# Relay_IO.net
KiCad netlist of a schematic drawn in Altium Designer
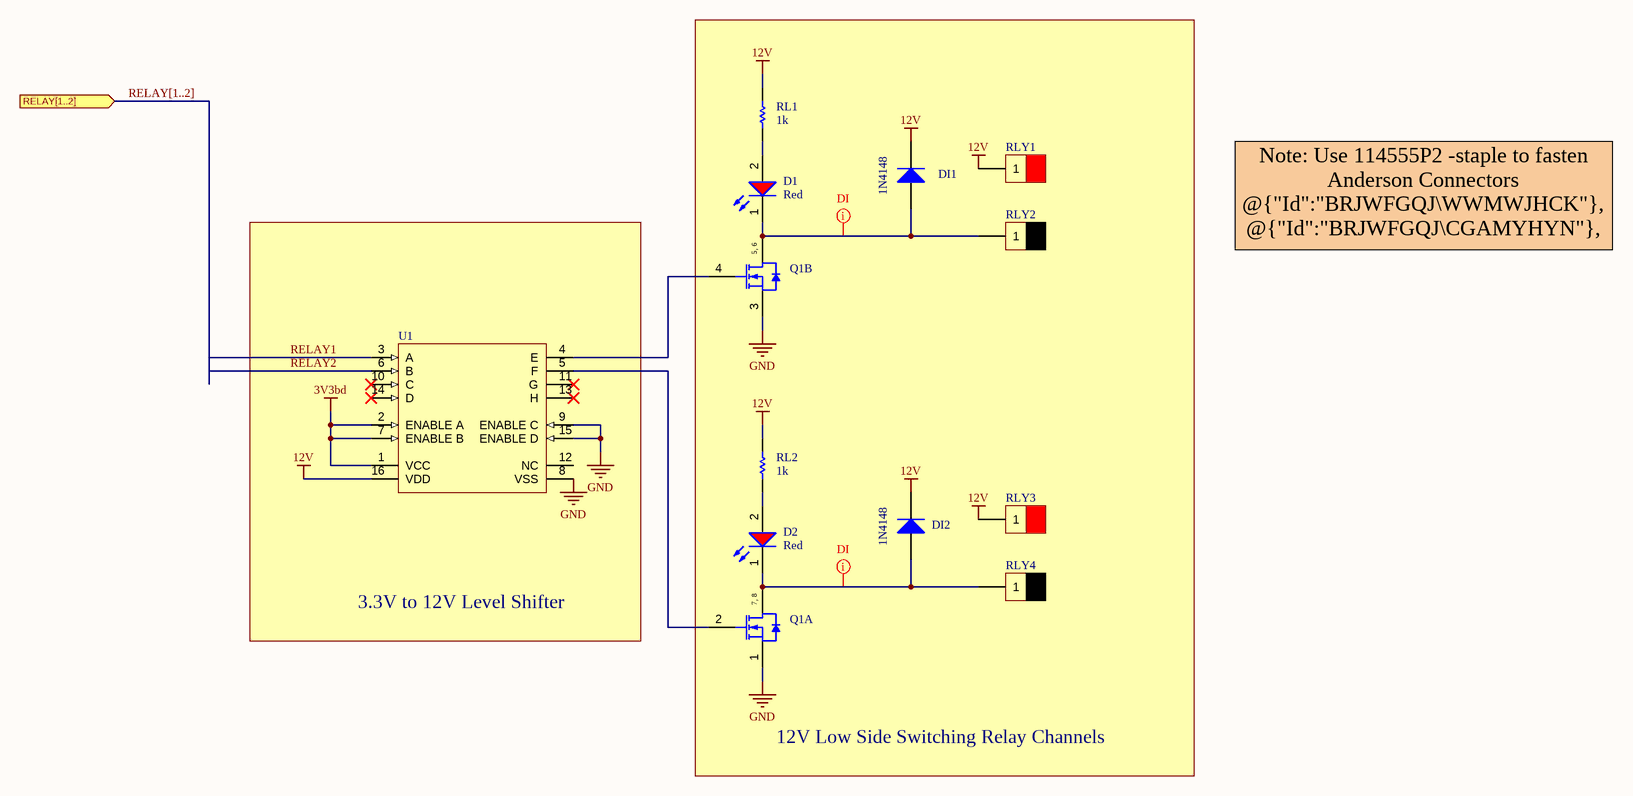
[diagram p0: Relay_IO.SchDoc]

(export (version "E")
  (design (tool "Eeschema 10.0.6"))
  (components
    (comp (ref "D1")
      (value "LED_Red0603")
      (footprint "0603_A")
      (description "Single Color LED, Red, Water Clear, 1.1mm")
      (fields (field (name "COLOR") "Red"))
      (libsource (lib "Advanced] Training Course - A365") (part "LED_Red_2A-1K"))
    )
    (comp (ref "D2")
      (value "LED_Red0603")
      (footprint "0603_A")
      (description "Single Color LED, Red, Water Clear, 1.1mm")
      (fields (field (name "COLOR") "Red"))
      (libsource (lib "Advanced] Training Course - A365") (part "LED_Red_2A-1K"))
    )
    (comp (ref "DI1")
      (value "1N4148")
      (footprint "DO-41")
      (description "Rectifier Diode, 1 Phase, 1 Element, 1A, 100V V(RRM), Silicon, DO-41")
      (libsource (lib "Advanced] Training Course - A365") (part "Diode  General"))
    )
    (comp (ref "DI2")
      (value "1N4148")
      (footprint "DO-41")
      (description "Rectifier Diode, 1 Phase, 1 Element, 1A, 100V V(RRM), Silicon, DO-41")
      (libsource (lib "Advanced] Training Course - A365") (part "Diode  General"))
    )
    (comp (ref "Q1")
      (value "NTHD4508NT1")
      (footprint "ONSC-CHIPFET-8-1206A-03_S2_V")
      (description "Small Signal Field-Effect Transistor")
      (libsource (lib "Advanced] Training Course - A365") (part "MOSFET Dual N-Channel"))
    )
    (comp (ref "RL1")
      (value "Res1K_0805")
      (footprint "0805_L")
      (fields
        (field (name "MANUFACTURER") "Panasonic Electronic Components")
        (field (name "MANUFACTURER PART NUMBER") "ERJ-6GEYJ102V")
        (field (name "RESISTANCE (OHMS)") "1k")
        (field (name "TOLERANCE") "5%")
      )
      (libsource (lib "Advanced] Training Course - A365") (part "Resistor General"))
    )
    (comp (ref "RL2")
      (value "Res1K_0805")
      (footprint "0805_L")
      (fields
        (field (name "MANUFACTURER") "Panasonic Electronic Components")
        (field (name "MANUFACTURER PART NUMBER") "ERJ-6GEYJ102V")
        (field (name "RESISTANCE (OHMS)") "1k")
        (field (name "TOLERANCE") "5%")
      )
      (libsource (lib "Advanced] Training Course - A365") (part "Resistor General"))
    )
    (comp (ref "RLY1")
      (value "Anderson-1Pin RED_PCB_RHT")
      (footprint "Anderson_RED_RHT_BOT")
      (description "Connector Accessory, Contact, Copper Alloy")
      (libsource (lib "TC - Altium Essentials Course A365 13") (part "Anderson-1Pin RED_PCB_RHT"))
    )
    (comp (ref "RLY2")
      (value "Anderson-1Pin BLK_PCB_RHT")
      (footprint "Anderson_BLK_RHT_BOT")
      (description "Connector Accessory, Contact, Copper Alloy")
      (libsource (lib "Advanced] Training Course - A365") (part "Anderson-1Pin BLK_PCB_RHT"))
    )
    (comp (ref "RLY3")
      (value "Anderson-1Pin RED_PCB_RHT")
      (footprint "Anderson_RED_RHT_BOT")
      (description "Connector Accessory, Contact, Copper Alloy")
      (libsource (lib "TC - Altium Essentials Course A365 13") (part "Anderson-1Pin RED_PCB_RHT"))
    )
    (comp (ref "RLY4")
      (value "Anderson-1Pin BLK_PCB_RHT")
      (footprint "Anderson_BLK_RHT_BOT")
      (description "Connector Accessory, Contact, Copper Alloy")
      (libsource (lib "Advanced] Training Course - A365") (part "Anderson-1Pin BLK_PCB_RHT"))
    )
    (comp (ref "U1")
      (value "CD40109BPW")
      (footprint "PW0016A_M")
      (fields
        (field (name "MANUFACTURER") "Texas Instruments")
        (field (name "MANUFACTURER PART NUMBER") "CD40109BPWR")
        (field (name "AVAILABLE PREVIEW IMAGES") "2D")
      )
      (libsource (lib "Advanced] Training Course - A365") (part "CD40109BPW"))
    )
  )
  (nets
    (net (code "1") (name "/RELAY1") (class "Default")
      (node (ref "U1") (pin "3") (pinfunction "A_3") (pintype "input"))
    )
    (net (code "2") (name "/RELAY2") (class "Default")
      (node (ref "U1") (pin "6") (pinfunction "B_6") (pintype "input"))
    )
    (net (code "4") (name "3V3bd") (class "Default")
      (node (ref "U1") (pin "1") (pinfunction "VCC_1") (pintype "power_in"))
      (node (ref "U1") (pin "2") (pinfunction "ENABLE_A_2") (pintype "input"))
      (node (ref "U1") (pin "7") (pinfunction "ENABLE_B_7") (pintype "input"))
    )
    (net (code "5") (name "12V") (class "Default")
      (node (ref "DI1") (pin "2") (pinfunction "K_2") (pintype "passive"))
      (node (ref "DI2") (pin "2") (pinfunction "K_2") (pintype "passive"))
      (node (ref "RL1") (pin "2") (pinfunction "2_2") (pintype "passive"))
      (node (ref "RL2") (pin "2") (pinfunction "2_2") (pintype "passive"))
      (node (ref "RLY1") (pin "1") (pinfunction "1_1") (pintype "passive"))
      (node (ref "RLY3") (pin "1") (pinfunction "1_1") (pintype "passive"))
      (node (ref "U1") (pin "16") (pinfunction "VDD_16") (pintype "power_in"))
    )
    (net (code "6") (name "GND") (class "Default")
      (node (ref "Q1") (pin "1") (pinfunction "S1_1") (pintype "passive"))
      (node (ref "Q1") (pin "3") (pinfunction "S2_3") (pintype "passive"))
      (node (ref "U1") (pin "15") (pinfunction "ENABLE_D_15") (pintype "input"))
      (node (ref "U1") (pin "8") (pinfunction "VSS_8") (pintype "power_in"))
      (node (ref "U1") (pin "9") (pinfunction "ENABLE_C_9") (pintype "input"))
    )
    (net (code "7") (name "Net-(D1-A)") (class "Default")
      (node (ref "D1") (pin "2") (pinfunction "A_2") (pintype "passive"))
      (node (ref "RL1") (pin "1") (pinfunction "1_1") (pintype "passive"))
    )
    (net (code "8") (name "Net-(D1-K)") (class "Default")
      (node (ref "D1") (pin "1") (pinfunction "K_1") (pintype "passive"))
      (node (ref "DI1") (pin "1") (pinfunction "A_1") (pintype "passive"))
      (node (ref "Q1") (pin "5") (pinfunction "D2_5") (pintype "passive"))
      (node (ref "Q1") (pin "6") (pinfunction "D2_6") (pintype "passive"))
      (node (ref "RLY2") (pin "1") (pinfunction "1_1") (pintype "passive"))
    )
    (net (code "9") (name "Net-(D2-A)") (class "Default")
      (node (ref "D2") (pin "2") (pinfunction "A_2") (pintype "passive"))
      (node (ref "RL2") (pin "1") (pinfunction "1_1") (pintype "passive"))
    )
    (net (code "10") (name "Net-(D2-K)") (class "Default")
      (node (ref "D2") (pin "1") (pinfunction "K_1") (pintype "passive"))
      (node (ref "DI2") (pin "1") (pinfunction "A_1") (pintype "passive"))
      (node (ref "Q1") (pin "7") (pinfunction "D1_7") (pintype "passive"))
      (node (ref "Q1") (pin "8") (pinfunction "D1_8") (pintype "passive"))
      (node (ref "RLY4") (pin "1") (pinfunction "1_1") (pintype "passive"))
    )
    (net (code "11") (name "Net-(Q1A-G1)") (class "Default")
      (node (ref "Q1") (pin "2") (pinfunction "G1_2") (pintype "passive"))
      (node (ref "U1") (pin "5") (pinfunction "F_5") (pintype "tri_state"))
    )
    (net (code "12") (name "Net-(Q1B-G2)") (class "Default")
      (node (ref "Q1") (pin "4") (pinfunction "G2_4") (pintype "passive"))
      (node (ref "U1") (pin "4") (pinfunction "E_4") (pintype "tri_state"))
    )
    (net (code "13") (name "unconnected-(U1-C-Pad10)") (class "Default")
      (node (ref "U1") (pin "10") (pinfunction "C_10") (pintype "input+no_connect"))
    )
    (net (code "14") (name "unconnected-(U1-D-Pad14)") (class "Default")
      (node (ref "U1") (pin "14") (pinfunction "D_14") (pintype "input+no_connect"))
    )
    (net (code "15") (name "unconnected-(U1-G-Pad11)") (class "Default")
      (node (ref "U1") (pin "11") (pinfunction "G_11") (pintype "tri_state+no_connect"))
    )
    (net (code "16") (name "unconnected-(U1-H-Pad13)") (class "Default")
      (node (ref "U1") (pin "13") (pinfunction "H_13") (pintype "tri_state+no_connect"))
    )
    (net (code "17") (name "unconnected-(U1-NC-Pad12)") (class "Default")
      (node (ref "U1") (pin "12") (pinfunction "NC_12") (pintype "passive"))
    )
  )
)
